# PS_Ethernet.net
KiCad netlist of a schematic drawn in Altium Designer
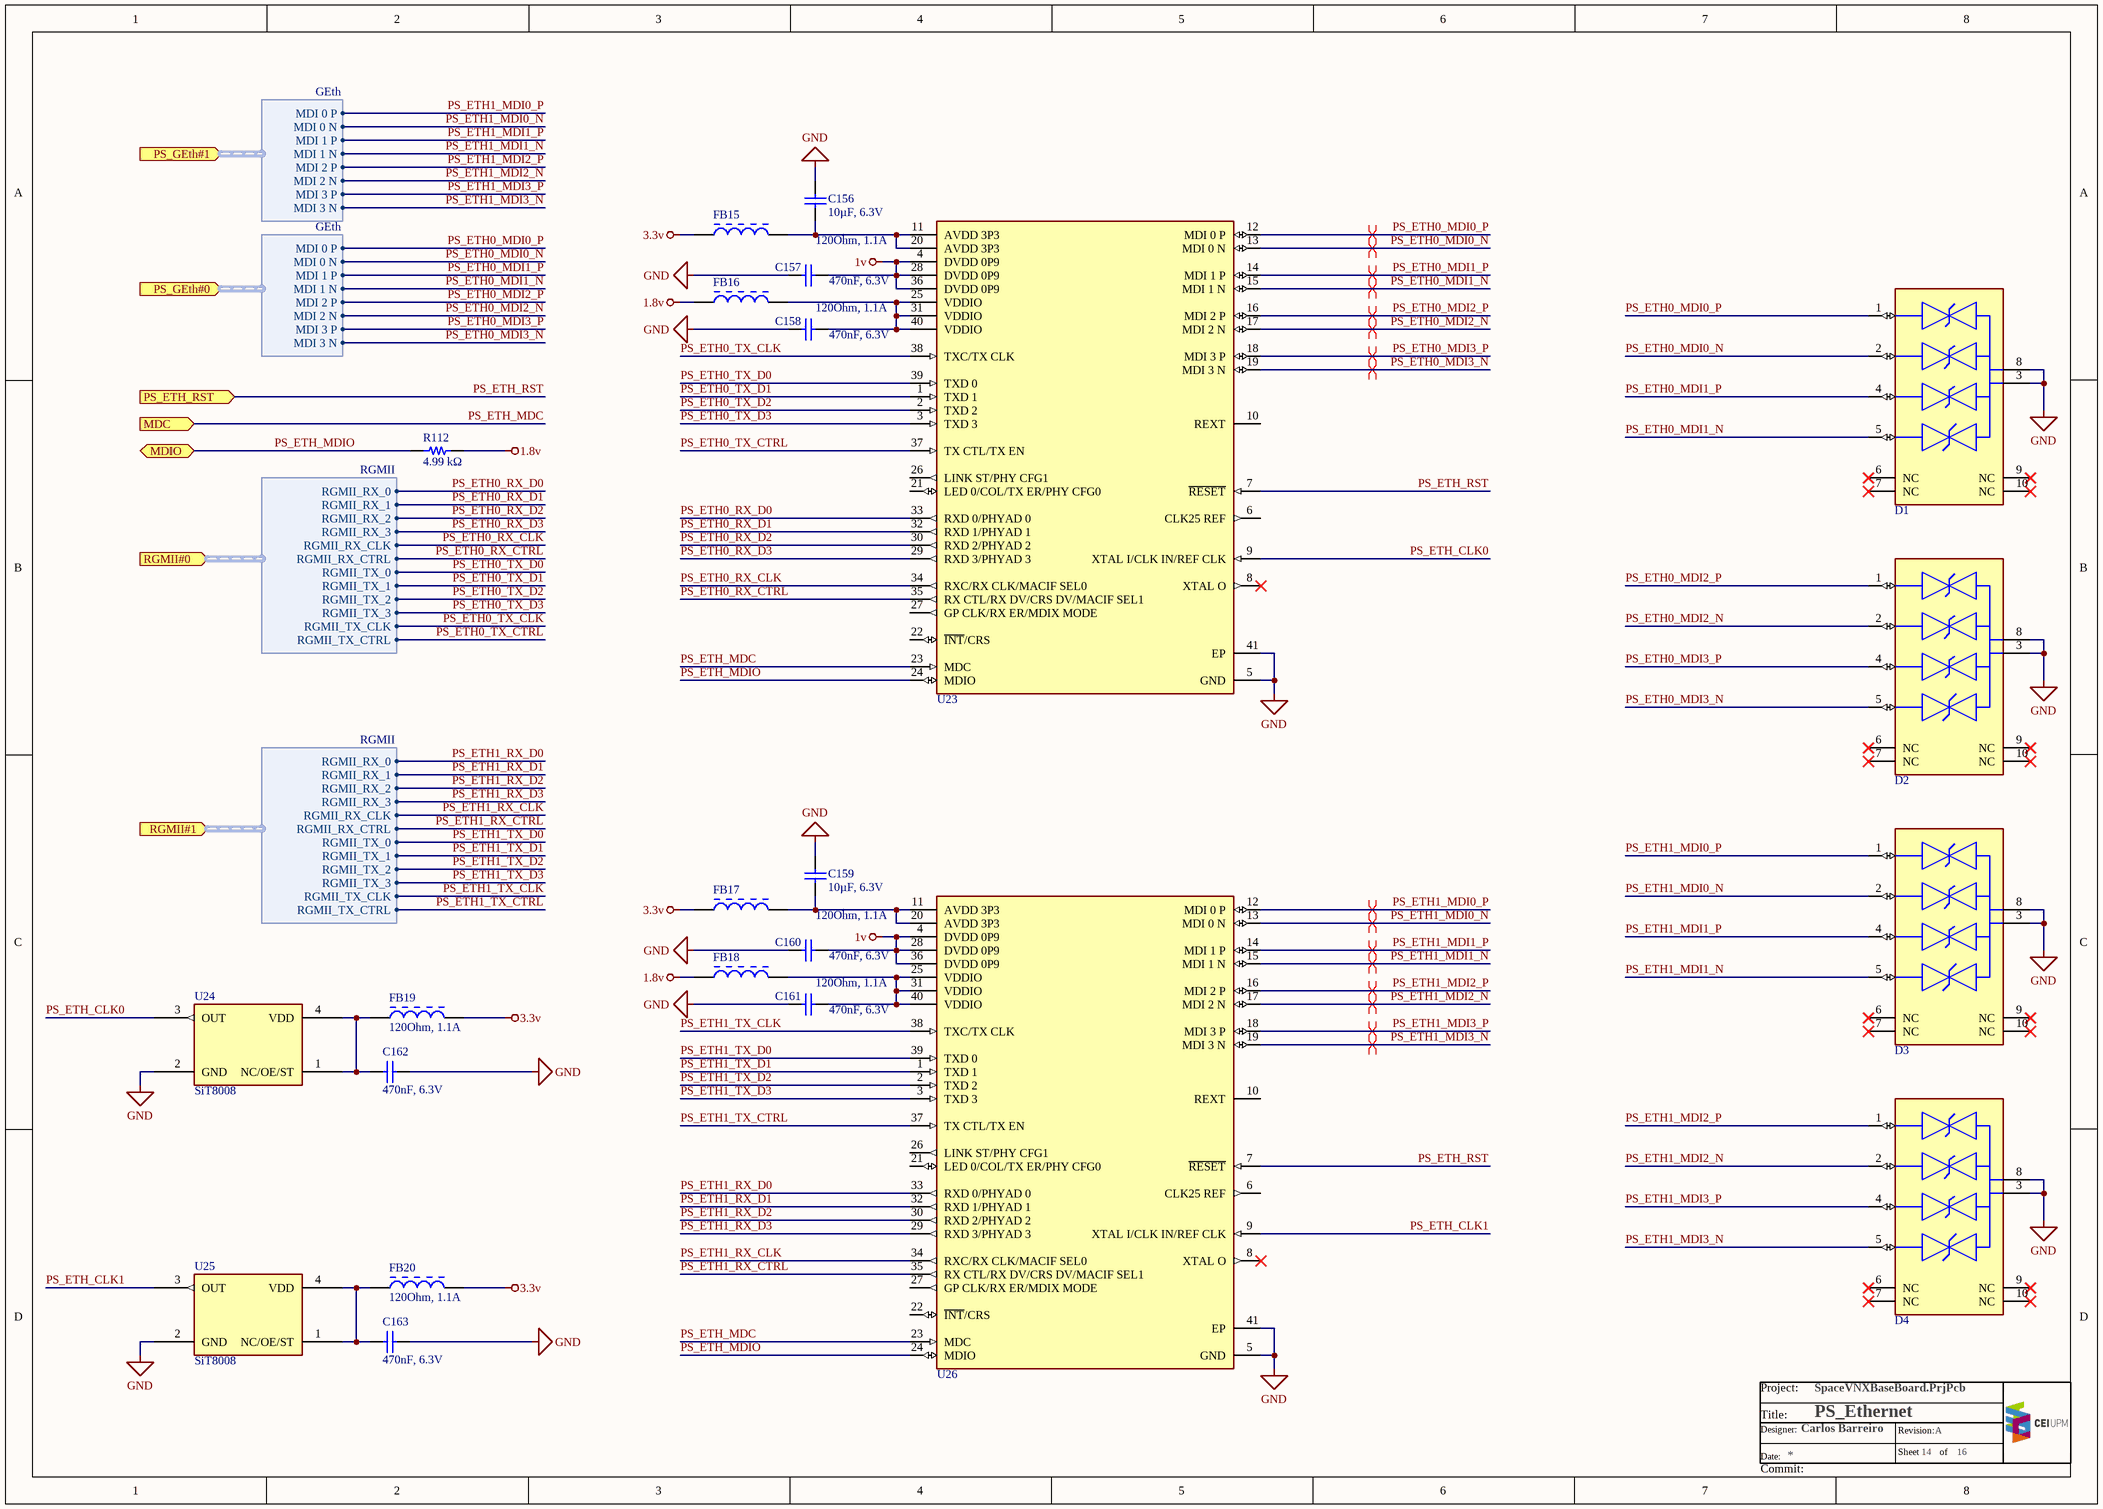
[diagram p0: PS_Ethernet.SchDoc]

(export (version "E")
  (design (tool "Eeschema 10.0.6"))
  (components
    (comp (ref "C156")
      (value "10µF, 6.3V")
      (footprint "WURTH_WCAP-CSGP_0402")
      (description "WCAP-CSGP Multilayer Ceramic Chip Capacitor, General Purpose, size 0402, X5R, 10uF, 6.3V")
      (fields
        (field (name "MANUFACTURER PART NUMBER") "885012105020")
        (field (name "MANUFACTURER") "Wurth Elektronik")
      )
      (libsource (lib "SpaceVNX") (part "885012105020"))
    )
    (comp (ref "C157")
      (value "470nF, 6.3V")
      (footprint "WURTH_WCAP-CSGP_0402")
      (description "WCAP-CSGP Multilayer Ceramic Chip Capacitor, General Purpose, size 0402, X5R, 470nF, 6.3V")
      (fields
        (field (name "MANUFACTURER PART NUMBER") "885012105004")
        (field (name "MANUFACTURER") "Wurth Elektronik")
      )
      (libsource (lib "SpaceVNX") (part "885012105004"))
    )
    (comp (ref "C158")
      (value "470nF, 6.3V")
      (footprint "WURTH_WCAP-CSGP_0402")
      (description "WCAP-CSGP Multilayer Ceramic Chip Capacitor, General Purpose, size 0402, X5R, 470nF, 6.3V")
      (fields
        (field (name "MANUFACTURER PART NUMBER") "885012105004")
        (field (name "MANUFACTURER") "Wurth Elektronik")
      )
      (libsource (lib "SpaceVNX") (part "885012105004"))
    )
    (comp (ref "C159")
      (value "10µF, 6.3V")
      (footprint "WURTH_WCAP-CSGP_0402")
      (description "WCAP-CSGP Multilayer Ceramic Chip Capacitor, General Purpose, size 0402, X5R, 10uF, 6.3V")
      (fields
        (field (name "MANUFACTURER PART NUMBER") "885012105020")
        (field (name "MANUFACTURER") "Wurth Elektronik")
      )
      (libsource (lib "SpaceVNX") (part "885012105020"))
    )
    (comp (ref "C160")
      (value "470nF, 6.3V")
      (footprint "WURTH_WCAP-CSGP_0402")
      (description "WCAP-CSGP Multilayer Ceramic Chip Capacitor, General Purpose, size 0402, X5R, 470nF, 6.3V")
      (fields
        (field (name "MANUFACTURER PART NUMBER") "885012105004")
        (field (name "MANUFACTURER") "Wurth Elektronik")
      )
      (libsource (lib "SpaceVNX") (part "885012105004"))
    )
    (comp (ref "C161")
      (value "470nF, 6.3V")
      (footprint "WURTH_WCAP-CSGP_0402")
      (description "WCAP-CSGP Multilayer Ceramic Chip Capacitor, General Purpose, size 0402, X5R, 470nF, 6.3V")
      (fields
        (field (name "MANUFACTURER PART NUMBER") "885012105004")
        (field (name "MANUFACTURER") "Wurth Elektronik")
      )
      (libsource (lib "SpaceVNX") (part "885012105004"))
    )
    (comp (ref "C162")
      (value "470nF, 6.3V")
      (footprint "WURTH_WCAP-CSGP_0402")
      (description "WCAP-CSGP Multilayer Ceramic Chip Capacitor, General Purpose, size 0402, X5R, 470nF, 6.3V")
      (fields
        (field (name "MANUFACTURER PART NUMBER") "885012105004")
        (field (name "MANUFACTURER") "Wurth Elektronik")
      )
      (libsource (lib "SpaceVNX") (part "885012105004"))
    )
    (comp (ref "C163")
      (value "470nF, 6.3V")
      (footprint "WURTH_WCAP-CSGP_0402")
      (description "WCAP-CSGP Multilayer Ceramic Chip Capacitor, General Purpose, size 0402, X5R, 470nF, 6.3V")
      (fields
        (field (name "MANUFACTURER PART NUMBER") "885012105004")
        (field (name "MANUFACTURER") "Wurth Elektronik")
      )
      (libsource (lib "SpaceVNX") (part "885012105004"))
    )
    (comp (ref "D1")
      (value "ESD204DQAR")
      (footprint "TEXAS_USON10")
      (description "ESD204 4-Channel Low-Capacitance Surge and ESD Protection Diode")
      (libsource (lib "SpaceVNX") (part "ESD204DQAR"))
    )
    (comp (ref "D2")
      (value "ESD204DQAR")
      (footprint "TEXAS_USON10")
      (description "ESD204 4-Channel Low-Capacitance Surge and ESD Protection Diode")
      (libsource (lib "SpaceVNX") (part "ESD204DQAR"))
    )
    (comp (ref "D3")
      (value "ESD204DQAR")
      (footprint "TEXAS_USON10")
      (description "ESD204 4-Channel Low-Capacitance Surge and ESD Protection Diode")
      (libsource (lib "SpaceVNX") (part "ESD204DQAR"))
    )
    (comp (ref "D4")
      (value "ESD204DQAR")
      (footprint "TEXAS_USON10")
      (description "ESD204 4-Channel Low-Capacitance Surge and ESD Protection Diode")
      (libsource (lib "SpaceVNX") (part "ESD204DQAR"))
    )
    (comp (ref "FB15")
      (value "120Ohm, 1.1A")
      (footprint "WURTH-CBF_0402")
      (description "WE-CBF SMT EMI Suppression Ferrite Bead, size 0402, 120Ohm, 1.1A")
      (fields
        (field (name "MANUFACTURER PART NUMBER") "74279271")
        (field (name "MANUFACTURER") "Wurth Elektronik")
      )
      (libsource (lib "SpaceVNX") (part "74279271"))
    )
    (comp (ref "FB16")
      (value "120Ohm, 1.1A")
      (footprint "WURTH-CBF_0402")
      (description "WE-CBF SMT EMI Suppression Ferrite Bead, size 0402, 120Ohm, 1.1A")
      (fields
        (field (name "MANUFACTURER PART NUMBER") "74279271")
        (field (name "MANUFACTURER") "Wurth Elektronik")
      )
      (libsource (lib "SpaceVNX") (part "74279271"))
    )
    (comp (ref "FB17")
      (value "120Ohm, 1.1A")
      (footprint "WURTH-CBF_0402")
      (description "WE-CBF SMT EMI Suppression Ferrite Bead, size 0402, 120Ohm, 1.1A")
      (fields
        (field (name "MANUFACTURER PART NUMBER") "74279271")
        (field (name "MANUFACTURER") "Wurth Elektronik")
      )
      (libsource (lib "SpaceVNX") (part "74279271"))
    )
    (comp (ref "FB18")
      (value "120Ohm, 1.1A")
      (footprint "WURTH-CBF_0402")
      (description "WE-CBF SMT EMI Suppression Ferrite Bead, size 0402, 120Ohm, 1.1A")
      (fields
        (field (name "MANUFACTURER PART NUMBER") "74279271")
        (field (name "MANUFACTURER") "Wurth Elektronik")
      )
      (libsource (lib "SpaceVNX") (part "74279271"))
    )
    (comp (ref "FB19")
      (value "120Ohm, 1.1A")
      (footprint "WURTH-CBF_0402")
      (description "WE-CBF SMT EMI Suppression Ferrite Bead, size 0402, 120Ohm, 1.1A")
      (fields
        (field (name "MANUFACTURER PART NUMBER") "74279271")
        (field (name "MANUFACTURER") "Wurth Elektronik")
      )
      (libsource (lib "SpaceVNX") (part "74279271"))
    )
    (comp (ref "FB20")
      (value "120Ohm, 1.1A")
      (footprint "WURTH-CBF_0402")
      (description "WE-CBF SMT EMI Suppression Ferrite Bead, size 0402, 120Ohm, 1.1A")
      (fields
        (field (name "MANUFACTURER PART NUMBER") "74279271")
        (field (name "MANUFACTURER") "Wurth Elektronik")
      )
      (libsource (lib "SpaceVNX") (part "74279271"))
    )
    (comp (ref "R112")
      (value "4.99 kΩ")
      (footprint "PANASONIC_ERJ2G_0402")
      (description "General Purpose Thick Film Chip Resistors")
      (fields (field (name "MANUFACTURER") "Panasonic"))
      (libsource (lib "SpaceVNX") (part "ERJ2RKF4991X"))
    )
    (comp (ref "U23")
      (value "ADIN1300CCPZ")
      (footprint "ADI_LFCSP40")
      (description "Robust, Industrial, Low Latency and Low Power 10 Mbps, 100 Mbps, and 1 Gbps Ethernet PHY")
      (libsource (lib "SpaceVNX") (part "ADIN1300CCPZ"))
    )
    (comp (ref "U24")
      (value "SiT8008")
      (footprint "SiTime_5032_4")
      (libsource (lib "SpaceVNX") (part "SiT8008"))
    )
    (comp (ref "U25")
      (value "SiT8008")
      (footprint "SiTime_5032_4")
      (libsource (lib "SpaceVNX") (part "SiT8008"))
    )
    (comp (ref "U26")
      (value "ADIN1300CCPZ")
      (footprint "ADI_LFCSP40")
      (description "Robust, Industrial, Low Latency and Low Power 10 Mbps, 100 Mbps, and 1 Gbps Ethernet PHY")
      (libsource (lib "SpaceVNX") (part "ADIN1300CCPZ"))
    )
  )
  (nets
    (net (code "3") (name "/PS_ETH0_MDI0_N") (class "Default")
      (node (ref "D1") (pin "2") (pinfunction "IO2_2") (pintype "bidirectional"))
      (node (ref "U23") (pin "13") (pinfunction "MDI_0_N_13") (pintype "bidirectional"))
    )
    (net (code "4") (name "/PS_ETH0_MDI0_P") (class "Default")
      (node (ref "D1") (pin "1") (pinfunction "IO1_1") (pintype "bidirectional"))
      (node (ref "U23") (pin "12") (pinfunction "MDI_0_P_12") (pintype "bidirectional"))
    )
    (net (code "5") (name "/PS_ETH0_MDI1_N") (class "Default")
      (node (ref "D1") (pin "5") (pinfunction "IO4_5") (pintype "bidirectional"))
      (node (ref "U23") (pin "15") (pinfunction "MDI_1_N_15") (pintype "bidirectional"))
    )
    (net (code "6") (name "/PS_ETH0_MDI1_P") (class "Default")
      (node (ref "D1") (pin "4") (pinfunction "IO3_4") (pintype "bidirectional"))
      (node (ref "U23") (pin "14") (pinfunction "MDI_1_P_14") (pintype "bidirectional"))
    )
    (net (code "7") (name "/PS_ETH0_MDI2_N") (class "Default")
      (node (ref "D2") (pin "2") (pinfunction "IO2_2") (pintype "bidirectional"))
      (node (ref "U23") (pin "17") (pinfunction "MDI_2_N_17") (pintype "bidirectional"))
    )
    (net (code "8") (name "/PS_ETH0_MDI2_P") (class "Default")
      (node (ref "D2") (pin "1") (pinfunction "IO1_1") (pintype "bidirectional"))
      (node (ref "U23") (pin "16") (pinfunction "MDI_2_P_16") (pintype "bidirectional"))
    )
    (net (code "9") (name "/PS_ETH0_MDI3_N") (class "Default")
      (node (ref "D2") (pin "5") (pinfunction "IO4_5") (pintype "bidirectional"))
      (node (ref "U23") (pin "19") (pinfunction "MDI_3_N_19") (pintype "bidirectional"))
    )
    (net (code "10") (name "/PS_ETH0_MDI3_P") (class "Default")
      (node (ref "D2") (pin "4") (pinfunction "IO3_4") (pintype "bidirectional"))
      (node (ref "U23") (pin "18") (pinfunction "MDI_3_P_18") (pintype "bidirectional"))
    )
    (net (code "11") (name "/PS_ETH0_RX_CLK") (class "Default")
      (node (ref "U23") (pin "34") (pinfunction "RXC/RX_CLK/MACIF_SEL0_34") (pintype "output"))
    )
    (net (code "12") (name "/PS_ETH0_RX_CTRL") (class "Default")
      (node (ref "U23") (pin "35") (pinfunction "RX_CTL/RX_DV/CRS_DV/MACIF_SEL1_35") (pintype "output"))
    )
    (net (code "13") (name "/PS_ETH0_RX_D0") (class "Default")
      (node (ref "U23") (pin "33") (pinfunction "RXD_0/PHYAD_0_33") (pintype "output"))
    )
    (net (code "14") (name "/PS_ETH0_RX_D1") (class "Default")
      (node (ref "U23") (pin "32") (pinfunction "RXD_1/PHYAD_1_32") (pintype "output"))
    )
    (net (code "15") (name "/PS_ETH0_RX_D2") (class "Default")
      (node (ref "U23") (pin "30") (pinfunction "RXD_2/PHYAD_2_30") (pintype "output"))
    )
    (net (code "16") (name "/PS_ETH0_RX_D3") (class "Default")
      (node (ref "U23") (pin "29") (pinfunction "RXD_3/PHYAD_3_29") (pintype "output"))
    )
    (net (code "17") (name "/PS_ETH0_TX_CLK") (class "Default")
      (node (ref "U23") (pin "38") (pinfunction "TXC/TX_CLK_38") (pintype "input"))
    )
    (net (code "18") (name "/PS_ETH0_TX_CTRL") (class "Default")
      (node (ref "U23") (pin "37") (pinfunction "TX_CTL/TX_EN_37") (pintype "input"))
    )
    (net (code "19") (name "/PS_ETH0_TX_D0") (class "Default")
      (node (ref "U23") (pin "39") (pinfunction "TXD_0_39") (pintype "input"))
    )
    (net (code "20") (name "/PS_ETH0_TX_D1") (class "Default")
      (node (ref "U23") (pin "1") (pinfunction "TXD_1_1") (pintype "input"))
    )
    (net (code "21") (name "/PS_ETH0_TX_D2") (class "Default")
      (node (ref "U23") (pin "2") (pinfunction "TXD_2_2") (pintype "input"))
    )
    (net (code "22") (name "/PS_ETH0_TX_D3") (class "Default")
      (node (ref "U23") (pin "3") (pinfunction "TXD_3_3") (pintype "input"))
    )
    (net (code "23") (name "/PS_ETH1_MDI0_N") (class "Default")
      (node (ref "D3") (pin "2") (pinfunction "IO2_2") (pintype "bidirectional"))
      (node (ref "U26") (pin "13") (pinfunction "MDI_0_N_13") (pintype "bidirectional"))
    )
    (net (code "24") (name "/PS_ETH1_MDI0_P") (class "Default")
      (node (ref "D3") (pin "1") (pinfunction "IO1_1") (pintype "bidirectional"))
      (node (ref "U26") (pin "12") (pinfunction "MDI_0_P_12") (pintype "bidirectional"))
    )
    (net (code "25") (name "/PS_ETH1_MDI1_N") (class "Default")
      (node (ref "D3") (pin "5") (pinfunction "IO4_5") (pintype "bidirectional"))
      (node (ref "U26") (pin "15") (pinfunction "MDI_1_N_15") (pintype "bidirectional"))
    )
    (net (code "26") (name "/PS_ETH1_MDI1_P") (class "Default")
      (node (ref "D3") (pin "4") (pinfunction "IO3_4") (pintype "bidirectional"))
      (node (ref "U26") (pin "14") (pinfunction "MDI_1_P_14") (pintype "bidirectional"))
    )
    (net (code "27") (name "/PS_ETH1_MDI2_N") (class "Default")
      (node (ref "D4") (pin "2") (pinfunction "IO2_2") (pintype "bidirectional"))
      (node (ref "U26") (pin "17") (pinfunction "MDI_2_N_17") (pintype "bidirectional"))
    )
    (net (code "28") (name "/PS_ETH1_MDI2_P") (class "Default")
      (node (ref "D4") (pin "1") (pinfunction "IO1_1") (pintype "bidirectional"))
      (node (ref "U26") (pin "16") (pinfunction "MDI_2_P_16") (pintype "bidirectional"))
    )
    (net (code "29") (name "/PS_ETH1_MDI3_N") (class "Default")
      (node (ref "D4") (pin "5") (pinfunction "IO4_5") (pintype "bidirectional"))
      (node (ref "U26") (pin "19") (pinfunction "MDI_3_N_19") (pintype "bidirectional"))
    )
    (net (code "30") (name "/PS_ETH1_MDI3_P") (class "Default")
      (node (ref "D4") (pin "4") (pinfunction "IO3_4") (pintype "bidirectional"))
      (node (ref "U26") (pin "18") (pinfunction "MDI_3_P_18") (pintype "bidirectional"))
    )
    (net (code "31") (name "/PS_ETH1_RX_CLK") (class "Default")
      (node (ref "U26") (pin "34") (pinfunction "RXC/RX_CLK/MACIF_SEL0_34") (pintype "output"))
    )
    (net (code "32") (name "/PS_ETH1_RX_CTRL") (class "Default")
      (node (ref "U26") (pin "35") (pinfunction "RX_CTL/RX_DV/CRS_DV/MACIF_SEL1_35") (pintype "output"))
    )
    (net (code "33") (name "/PS_ETH1_RX_D0") (class "Default")
      (node (ref "U26") (pin "33") (pinfunction "RXD_0/PHYAD_0_33") (pintype "output"))
    )
    (net (code "34") (name "/PS_ETH1_RX_D1") (class "Default")
      (node (ref "U26") (pin "32") (pinfunction "RXD_1/PHYAD_1_32") (pintype "output"))
    )
    (net (code "35") (name "/PS_ETH1_RX_D2") (class "Default")
      (node (ref "U26") (pin "30") (pinfunction "RXD_2/PHYAD_2_30") (pintype "output"))
    )
    (net (code "36") (name "/PS_ETH1_RX_D3") (class "Default")
      (node (ref "U26") (pin "29") (pinfunction "RXD_3/PHYAD_3_29") (pintype "output"))
    )
    (net (code "37") (name "/PS_ETH1_TX_CLK") (class "Default")
      (node (ref "U26") (pin "38") (pinfunction "TXC/TX_CLK_38") (pintype "input"))
    )
    (net (code "38") (name "/PS_ETH1_TX_CTRL") (class "Default")
      (node (ref "U26") (pin "37") (pinfunction "TX_CTL/TX_EN_37") (pintype "input"))
    )
    (net (code "39") (name "/PS_ETH1_TX_D0") (class "Default")
      (node (ref "U26") (pin "39") (pinfunction "TXD_0_39") (pintype "input"))
    )
    (net (code "40") (name "/PS_ETH1_TX_D1") (class "Default")
      (node (ref "U26") (pin "1") (pinfunction "TXD_1_1") (pintype "input"))
    )
    (net (code "41") (name "/PS_ETH1_TX_D2") (class "Default")
      (node (ref "U26") (pin "2") (pinfunction "TXD_2_2") (pintype "input"))
    )
    (net (code "42") (name "/PS_ETH1_TX_D3") (class "Default")
      (node (ref "U26") (pin "3") (pinfunction "TXD_3_3") (pintype "input"))
    )
    (net (code "43") (name "/PS_ETH_CLK0") (class "Default")
      (node (ref "U23") (pin "9") (pinfunction "XTAL_I/CLK_IN/REF_CLK_9") (pintype "input"))
      (node (ref "U24") (pin "3") (pinfunction "OUT_3") (pintype "output"))
    )
    (net (code "44") (name "/PS_ETH_CLK1") (class "Default")
      (node (ref "U25") (pin "3") (pinfunction "OUT_3") (pintype "output"))
      (node (ref "U26") (pin "9") (pinfunction "XTAL_I/CLK_IN/REF_CLK_9") (pintype "input"))
    )
    (net (code "45") (name "/PS_ETH_MDC") (class "Default")
      (node (ref "U23") (pin "23") (pinfunction "MDC_23") (pintype "input"))
      (node (ref "U26") (pin "23") (pinfunction "MDC_23") (pintype "input"))
    )
    (net (code "46") (name "/PS_ETH_MDIO") (class "Default")
      (node (ref "R112") (pin "1") (pinfunction "1_1") (pintype "passive"))
      (node (ref "U23") (pin "24") (pinfunction "MDIO_24") (pintype "bidirectional"))
      (node (ref "U26") (pin "24") (pinfunction "MDIO_24") (pintype "bidirectional"))
    )
    (net (code "47") (name "/PS_ETH_RST") (class "Default")
      (node (ref "U23") (pin "7") (pinfunction "~{RESET}_7") (pintype "input"))
      (node (ref "U26") (pin "7") (pinfunction "~{RESET}_7") (pintype "input"))
    )
    (net (code "50") (name "1.8v") (class "Default")
      (node (ref "FB16") (pin "1") (pinfunction "1_1") (pintype "passive"))
      (node (ref "FB18") (pin "1") (pinfunction "1_1") (pintype "passive"))
      (node (ref "R112") (pin "2") (pinfunction "2_2") (pintype "passive"))
    )
    (net (code "51") (name "1v") (class "Default")
      (node (ref "C157") (pin "2") (pinfunction "2_2") (pintype "passive"))
      (node (ref "C160") (pin "2") (pinfunction "2_2") (pintype "passive"))
      (node (ref "U23") (pin "28") (pinfunction "DVDD_0P9_28") (pintype "power_in"))
      (node (ref "U23") (pin "36") (pinfunction "DVDD_0P9_36") (pintype "power_in"))
      (node (ref "U23") (pin "4") (pinfunction "DVDD_0P9_4") (pintype "power_in"))
      (node (ref "U26") (pin "28") (pinfunction "DVDD_0P9_28") (pintype "power_in"))
      (node (ref "U26") (pin "36") (pinfunction "DVDD_0P9_36") (pintype "power_in"))
      (node (ref "U26") (pin "4") (pinfunction "DVDD_0P9_4") (pintype "power_in"))
    )
    (net (code "52") (name "3.3v") (class "Default")
      (node (ref "FB15") (pin "1") (pinfunction "1_1") (pintype "passive"))
      (node (ref "FB17") (pin "1") (pinfunction "1_1") (pintype "passive"))
      (node (ref "FB19") (pin "2") (pinfunction "2_2") (pintype "passive"))
      (node (ref "FB20") (pin "2") (pinfunction "2_2") (pintype "passive"))
    )
    (net (code "53") (name "GND") (class "Default")
      (node (ref "C156") (pin "2") (pinfunction "2_2") (pintype "passive"))
      (node (ref "C157") (pin "1") (pinfunction "1_1") (pintype "passive"))
      (node (ref "C158") (pin "1") (pinfunction "1_1") (pintype "passive"))
      (node (ref "C159") (pin "2") (pinfunction "2_2") (pintype "passive"))
      (node (ref "C160") (pin "1") (pinfunction "1_1") (pintype "passive"))
      (node (ref "C161") (pin "1") (pinfunction "1_1") (pintype "passive"))
      (node (ref "C162") (pin "1") (pinfunction "1_1") (pintype "passive"))
      (node (ref "C163") (pin "1") (pinfunction "1_1") (pintype "passive"))
      (node (ref "D1") (pin "3") (pinfunction "GND_3") (pintype "power_in"))
      (node (ref "D1") (pin "8") (pinfunction "GND_8") (pintype "power_in"))
      (node (ref "D2") (pin "3") (pinfunction "GND_3") (pintype "power_in"))
      (node (ref "D2") (pin "8") (pinfunction "GND_8") (pintype "power_in"))
      (node (ref "D3") (pin "3") (pinfunction "GND_3") (pintype "power_in"))
      (node (ref "D3") (pin "8") (pinfunction "GND_8") (pintype "power_in"))
      (node (ref "D4") (pin "3") (pinfunction "GND_3") (pintype "power_in"))
      (node (ref "D4") (pin "8") (pinfunction "GND_8") (pintype "power_in"))
      (node (ref "U23") (pin "41") (pinfunction "EP_41") (pintype "power_in"))
      (node (ref "U23") (pin "5") (pinfunction "GND_5") (pintype "power_in"))
      (node (ref "U24") (pin "2") (pinfunction "GND_2") (pintype "passive"))
      (node (ref "U25") (pin "2") (pinfunction "GND_2") (pintype "passive"))
      (node (ref "U26") (pin "41") (pinfunction "EP_41") (pintype "power_in"))
      (node (ref "U26") (pin "5") (pinfunction "GND_5") (pintype "power_in"))
    )
    (net (code "54") (name "Net-(C156-Pad1)") (class "Default")
      (node (ref "C156") (pin "1") (pinfunction "1_1") (pintype "passive"))
      (node (ref "FB15") (pin "2") (pinfunction "2_2") (pintype "passive"))
      (node (ref "U23") (pin "11") (pinfunction "AVDD_3P3_11") (pintype "power_in"))
      (node (ref "U23") (pin "20") (pinfunction "AVDD_3P3_20") (pintype "power_in"))
    )
    (net (code "55") (name "Net-(C158-Pad2)") (class "Default")
      (node (ref "C158") (pin "2") (pinfunction "2_2") (pintype "passive"))
      (node (ref "FB16") (pin "2") (pinfunction "2_2") (pintype "passive"))
      (node (ref "U23") (pin "25") (pinfunction "VDDIO_25") (pintype "power_in"))
      (node (ref "U23") (pin "31") (pinfunction "VDDIO_31") (pintype "power_in"))
      (node (ref "U23") (pin "40") (pinfunction "VDDIO_40") (pintype "power_in"))
    )
    (net (code "56") (name "Net-(C159-Pad1)") (class "Default")
      (node (ref "C159") (pin "1") (pinfunction "1_1") (pintype "passive"))
      (node (ref "FB17") (pin "2") (pinfunction "2_2") (pintype "passive"))
      (node (ref "U26") (pin "11") (pinfunction "AVDD_3P3_11") (pintype "power_in"))
      (node (ref "U26") (pin "20") (pinfunction "AVDD_3P3_20") (pintype "power_in"))
    )
    (net (code "57") (name "Net-(C161-Pad2)") (class "Default")
      (node (ref "C161") (pin "2") (pinfunction "2_2") (pintype "passive"))
      (node (ref "FB18") (pin "2") (pinfunction "2_2") (pintype "passive"))
      (node (ref "U26") (pin "25") (pinfunction "VDDIO_25") (pintype "power_in"))
      (node (ref "U26") (pin "31") (pinfunction "VDDIO_31") (pintype "power_in"))
      (node (ref "U26") (pin "40") (pinfunction "VDDIO_40") (pintype "power_in"))
    )
    (net (code "58") (name "Net-(U24-NC{slash}OE{slash}ST)") (class "Default")
      (node (ref "C162") (pin "2") (pinfunction "2_2") (pintype "passive"))
      (node (ref "FB19") (pin "1") (pinfunction "1_1") (pintype "passive"))
      (node (ref "U24") (pin "1") (pinfunction "NC/OE/ST_1") (pintype "passive"))
      (node (ref "U24") (pin "4") (pinfunction "VDD_4") (pintype "passive"))
    )
    (net (code "59") (name "Net-(U25-NC{slash}OE{slash}ST)") (class "Default")
      (node (ref "C163") (pin "2") (pinfunction "2_2") (pintype "passive"))
      (node (ref "FB20") (pin "1") (pinfunction "1_1") (pintype "passive"))
      (node (ref "U25") (pin "1") (pinfunction "NC/OE/ST_1") (pintype "passive"))
      (node (ref "U25") (pin "4") (pinfunction "VDD_4") (pintype "passive"))
    )
    (net (code "60") (name "unconnected-(D1-NC-Pad6)") (class "Default")
      (node (ref "D1") (pin "6") (pinfunction "NC_6") (pintype "passive+no_connect"))
    )
    (net (code "61") (name "unconnected-(D1-NC-Pad7)") (class "Default")
      (node (ref "D1") (pin "7") (pinfunction "NC_7") (pintype "passive+no_connect"))
    )
    (net (code "62") (name "unconnected-(D1-NC-Pad9)") (class "Default")
      (node (ref "D1") (pin "9") (pinfunction "NC_9") (pintype "passive+no_connect"))
    )
    (net (code "63") (name "unconnected-(D1-NC-Pad10)") (class "Default")
      (node (ref "D1") (pin "10") (pinfunction "NC_10") (pintype "passive+no_connect"))
    )
    (net (code "64") (name "unconnected-(D2-NC-Pad6)") (class "Default")
      (node (ref "D2") (pin "6") (pinfunction "NC_6") (pintype "passive+no_connect"))
    )
    (net (code "65") (name "unconnected-(D2-NC-Pad7)") (class "Default")
      (node (ref "D2") (pin "7") (pinfunction "NC_7") (pintype "passive+no_connect"))
    )
    (net (code "66") (name "unconnected-(D2-NC-Pad9)") (class "Default")
      (node (ref "D2") (pin "9") (pinfunction "NC_9") (pintype "passive+no_connect"))
    )
    (net (code "67") (name "unconnected-(D2-NC-Pad10)") (class "Default")
      (node (ref "D2") (pin "10") (pinfunction "NC_10") (pintype "passive+no_connect"))
    )
    (net (code "68") (name "unconnected-(D3-NC-Pad6)") (class "Default")
      (node (ref "D3") (pin "6") (pinfunction "NC_6") (pintype "passive+no_connect"))
    )
    (net (code "69") (name "unconnected-(D3-NC-Pad7)") (class "Default")
      (node (ref "D3") (pin "7") (pinfunction "NC_7") (pintype "passive+no_connect"))
    )
    (net (code "70") (name "unconnected-(D3-NC-Pad9)") (class "Default")
      (node (ref "D3") (pin "9") (pinfunction "NC_9") (pintype "passive+no_connect"))
    )
    (net (code "71") (name "unconnected-(D3-NC-Pad10)") (class "Default")
      (node (ref "D3") (pin "10") (pinfunction "NC_10") (pintype "passive+no_connect"))
    )
    (net (code "72") (name "unconnected-(D4-NC-Pad6)") (class "Default")
      (node (ref "D4") (pin "6") (pinfunction "NC_6") (pintype "passive+no_connect"))
    )
    (net (code "73") (name "unconnected-(D4-NC-Pad7)") (class "Default")
      (node (ref "D4") (pin "7") (pinfunction "NC_7") (pintype "passive+no_connect"))
    )
    (net (code "74") (name "unconnected-(D4-NC-Pad9)") (class "Default")
      (node (ref "D4") (pin "9") (pinfunction "NC_9") (pintype "passive+no_connect"))
    )
    (net (code "75") (name "unconnected-(D4-NC-Pad10)") (class "Default")
      (node (ref "D4") (pin "10") (pinfunction "NC_10") (pintype "passive+no_connect"))
    )
    (net (code "76") (name "unconnected-(U23-CLK25_REF-Pad6)") (class "Default")
      (node (ref "U23") (pin "6") (pinfunction "CLK25_REF_6") (pintype "output"))
    )
    (net (code "77") (name "unconnected-(U23-GP_CLK{slash}RX_ER{slash}MDIX_MODE-Pad27)") (class "Default")
      (node (ref "U23") (pin "27") (pinfunction "GP_CLK/RX_ER/MDIX_MODE_27") (pintype "output"))
    )
    (net (code "78") (name "unconnected-(U23-LED_0{slash}COL{slash}TX_ER{slash}PHY_CFG0-Pad21)") (class "Default")
      (node (ref "U23") (pin "21") (pinfunction "LED_0/COL/TX_ER/PHY_CFG0_21") (pintype "bidirectional"))
    )
    (net (code "79") (name "unconnected-(U23-LINK_ST{slash}PHY_CFG1-Pad26)") (class "Default")
      (node (ref "U23") (pin "26") (pinfunction "LINK_ST/PHY_CFG1_26") (pintype "output"))
    )
    (net (code "80") (name "unconnected-(U23-REXT-Pad10)") (class "Default")
      (node (ref "U23") (pin "10") (pinfunction "REXT_10") (pintype "passive"))
    )
    (net (code "81") (name "unconnected-(U23-XTAL_O-Pad8)") (class "Default")
      (node (ref "U23") (pin "8") (pinfunction "XTAL_O_8") (pintype "output+no_connect"))
    )
    (net (code "82") (name "unconnected-(U23-~{INT}{slash}CRS-Pad22)") (class "Default")
      (node (ref "U23") (pin "22") (pinfunction "~{INT}/CRS_22") (pintype "bidirectional"))
    )
    (net (code "83") (name "unconnected-(U26-CLK25_REF-Pad6)") (class "Default")
      (node (ref "U26") (pin "6") (pinfunction "CLK25_REF_6") (pintype "output"))
    )
    (net (code "84") (name "unconnected-(U26-GP_CLK{slash}RX_ER{slash}MDIX_MODE-Pad27)") (class "Default")
      (node (ref "U26") (pin "27") (pinfunction "GP_CLK/RX_ER/MDIX_MODE_27") (pintype "output"))
    )
    (net (code "85") (name "unconnected-(U26-LED_0{slash}COL{slash}TX_ER{slash}PHY_CFG0-Pad21)") (class "Default")
      (node (ref "U26") (pin "21") (pinfunction "LED_0/COL/TX_ER/PHY_CFG0_21") (pintype "bidirectional"))
    )
    (net (code "86") (name "unconnected-(U26-LINK_ST{slash}PHY_CFG1-Pad26)") (class "Default")
      (node (ref "U26") (pin "26") (pinfunction "LINK_ST/PHY_CFG1_26") (pintype "output"))
    )
    (net (code "87") (name "unconnected-(U26-REXT-Pad10)") (class "Default")
      (node (ref "U26") (pin "10") (pinfunction "REXT_10") (pintype "passive"))
    )
    (net (code "88") (name "unconnected-(U26-XTAL_O-Pad8)") (class "Default")
      (node (ref "U26") (pin "8") (pinfunction "XTAL_O_8") (pintype "output+no_connect"))
    )
    (net (code "89") (name "unconnected-(U26-~{INT}{slash}CRS-Pad22)") (class "Default")
      (node (ref "U26") (pin "22") (pinfunction "~{INT}/CRS_22") (pintype "bidirectional"))
    )
  )
)
